# MicroSD.net
KiCad netlist of a schematic drawn in Altium Designer
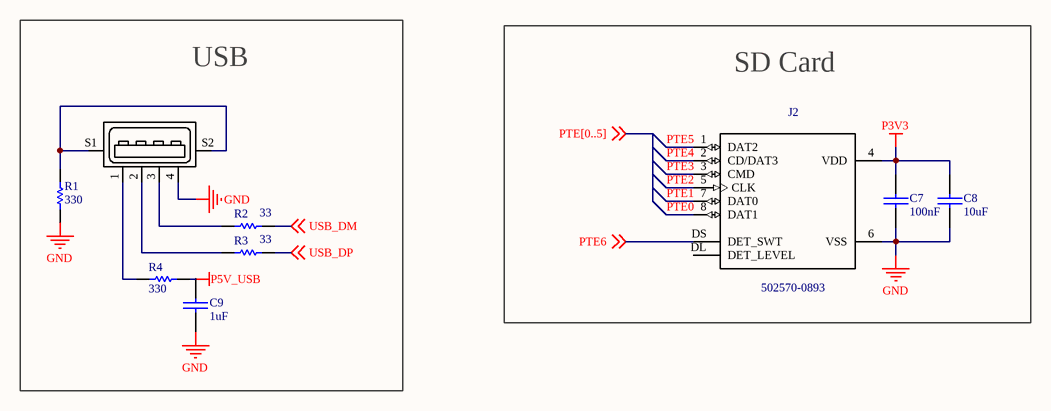
[diagram p0: MicroSD.SchDoc]

(export (version "E")
  (design (tool "Eeschema 10.0.6"))
  (components
    (comp (ref "C7") (value "100nF") (footprint "0805") (libsource (lib "LIBEBAL") (part "CAP")))
    (comp (ref "C8") (value "10uF") (footprint "0805") (libsource (lib "LIBEBAL") (part "CAP")))
    (comp (ref "C9") (value "1uF") (footprint "0805") (libsource (lib "LIBEBAL") (part "CAP")))
    (comp (ref "J1")
      (value "UJ2-AH-1-SMT")
      (footprint "CUI_UJ2-AH-1-SMT_UJ2-AH-1-SMT(Primary)")
      (description "Standard A type 4 pin Horizontal 3 Âµin Plating SMT USB 2.0 Jack")
      (fields (field (name "MP") "UJ2-AH-1-SMT-TR") (field (name "MF") "CUI Inc."))
      (libsource (lib "USB-A-SMT") (part "UJ2-AH-1-SMT"))
    )
    (comp (ref "J2")
      (value "502570-0893")
      (footprint "MOLEX_502570-0893_502570-0893(Primary)")
      (description "1.10mm Pitch microSD Memory Card Connector, Normal Mount Surface Mount, Push-Push Type")
      (fields (field (name "MF") "Molex"))
      (libsource (lib "MicroSD") (part "502570-0893"))
    )
    (comp (ref "R1") (value "330") (footprint "0805") (libsource (lib "LIBEBAL") (part "RES")))
    (comp (ref "R2") (value "33") (footprint "0805") (libsource (lib "LIBEBAL") (part "RES")))
    (comp (ref "R3") (value "33") (footprint "0805") (libsource (lib "LIBEBAL") (part "RES")))
    (comp (ref "R4") (value "330") (footprint "0805") (libsource (lib "LIBEBAL") (part "RES")))
  )
  (nets
    (net (code "1") (name "GND") (class "Default")
      (node (ref "C7") (pin "2") (pinfunction "2_2") (pintype "passive"))
      (node (ref "C8") (pin "2") (pinfunction "2_2") (pintype "passive"))
      (node (ref "C9") (pin "2") (pinfunction "2_2") (pintype "passive"))
      (node (ref "J1") (pin "4") (pinfunction "4_4") (pintype "passive"))
      (node (ref "J2") (pin "6") (pinfunction "VSS_6") (pintype "power_in"))
      (node (ref "R1") (pin "1") (pinfunction "1_1") (pintype "passive"))
    )
    (net (code "2") (name "Net-(J1-Pad1)") (class "Default")
      (node (ref "J1") (pin "1") (pinfunction "1_1") (pintype "passive"))
      (node (ref "R4") (pin "2") (pinfunction "2_2") (pintype "passive"))
    )
    (net (code "3") (name "Net-(J1-Pad2)") (class "Default")
      (node (ref "J1") (pin "2") (pinfunction "2_2") (pintype "passive"))
      (node (ref "R3") (pin "2") (pinfunction "2_2") (pintype "passive"))
    )
    (net (code "4") (name "Net-(J1-Pad3)") (class "Default")
      (node (ref "J1") (pin "3") (pinfunction "3_3") (pintype "passive"))
      (node (ref "R2") (pin "2") (pinfunction "2_2") (pintype "passive"))
    )
    (net (code "5") (name "Net-(J1-SHIELD-PadS1)") (class "Default")
      (node (ref "J1") (pin "S1") (pinfunction "SHIELD_S1") (pintype "passive"))
      (node (ref "J1") (pin "S2") (pinfunction "SHIELD_S2") (pintype "passive"))
      (node (ref "R1") (pin "2") (pinfunction "2_2") (pintype "passive"))
    )
    (net (code "6") (name "P3V3") (class "Default")
      (node (ref "C7") (pin "1") (pinfunction "1_1") (pintype "passive"))
      (node (ref "C8") (pin "1") (pinfunction "1_1") (pintype "passive"))
      (node (ref "J2") (pin "4") (pinfunction "VDD_4") (pintype "power_in"))
    )
    (net (code "7") (name "P5V_USB") (class "Default")
      (node (ref "R4") (pin "1") (pinfunction "1_1") (pintype "passive"))
    )
    (net (code "8") (name "PTE0") (class "Default")
      (node (ref "J2") (pin "8") (pinfunction "DAT1_8") (pintype "bidirectional"))
    )
    (net (code "9") (name "PTE1") (class "Default")
      (node (ref "J2") (pin "7") (pinfunction "DAT0_7") (pintype "bidirectional"))
    )
    (net (code "10") (name "PTE2") (class "Default")
      (node (ref "J2") (pin "5") (pinfunction "CLK_5") (pintype "input"))
    )
    (net (code "11") (name "PTE3") (class "Default")
      (node (ref "J2") (pin "3") (pinfunction "CMD_3") (pintype "bidirectional"))
    )
    (net (code "12") (name "PTE4") (class "Default")
      (node (ref "J2") (pin "2") (pinfunction "CD/DAT3_2") (pintype "bidirectional"))
    )
    (net (code "13") (name "PTE5") (class "Default")
      (node (ref "J2") (pin "1") (pinfunction "DAT2_1") (pintype "bidirectional"))
    )
    (net (code "14") (name "PTE6") (class "Default")
      (node (ref "J2") (pin "DS") (pinfunction "DET_SWT_DS") (pintype "passive"))
    )
    (net (code "16") (name "USB_DM") (class "Default")
      (node (ref "R2") (pin "1") (pinfunction "1_1") (pintype "passive"))
    )
    (net (code "17") (name "USB_DP") (class "Default")
      (node (ref "R3") (pin "1") (pinfunction "1_1") (pintype "passive"))
    )
    (net (code "18") (name "unconnected-(C9-Pad1)") (class "Default")
      (node (ref "C9") (pin "1") (pinfunction "1_1") (pintype "passive"))
    )
    (net (code "19") (name "unconnected-(J2-DET_LEVEL-PadDL)") (class "Default")
      (node (ref "J2") (pin "DL") (pinfunction "DET_LEVEL_DL") (pintype "passive"))
    )
  )
)
